# obd25k80.net
KiCad netlist of a schematic drawn in EAGLE
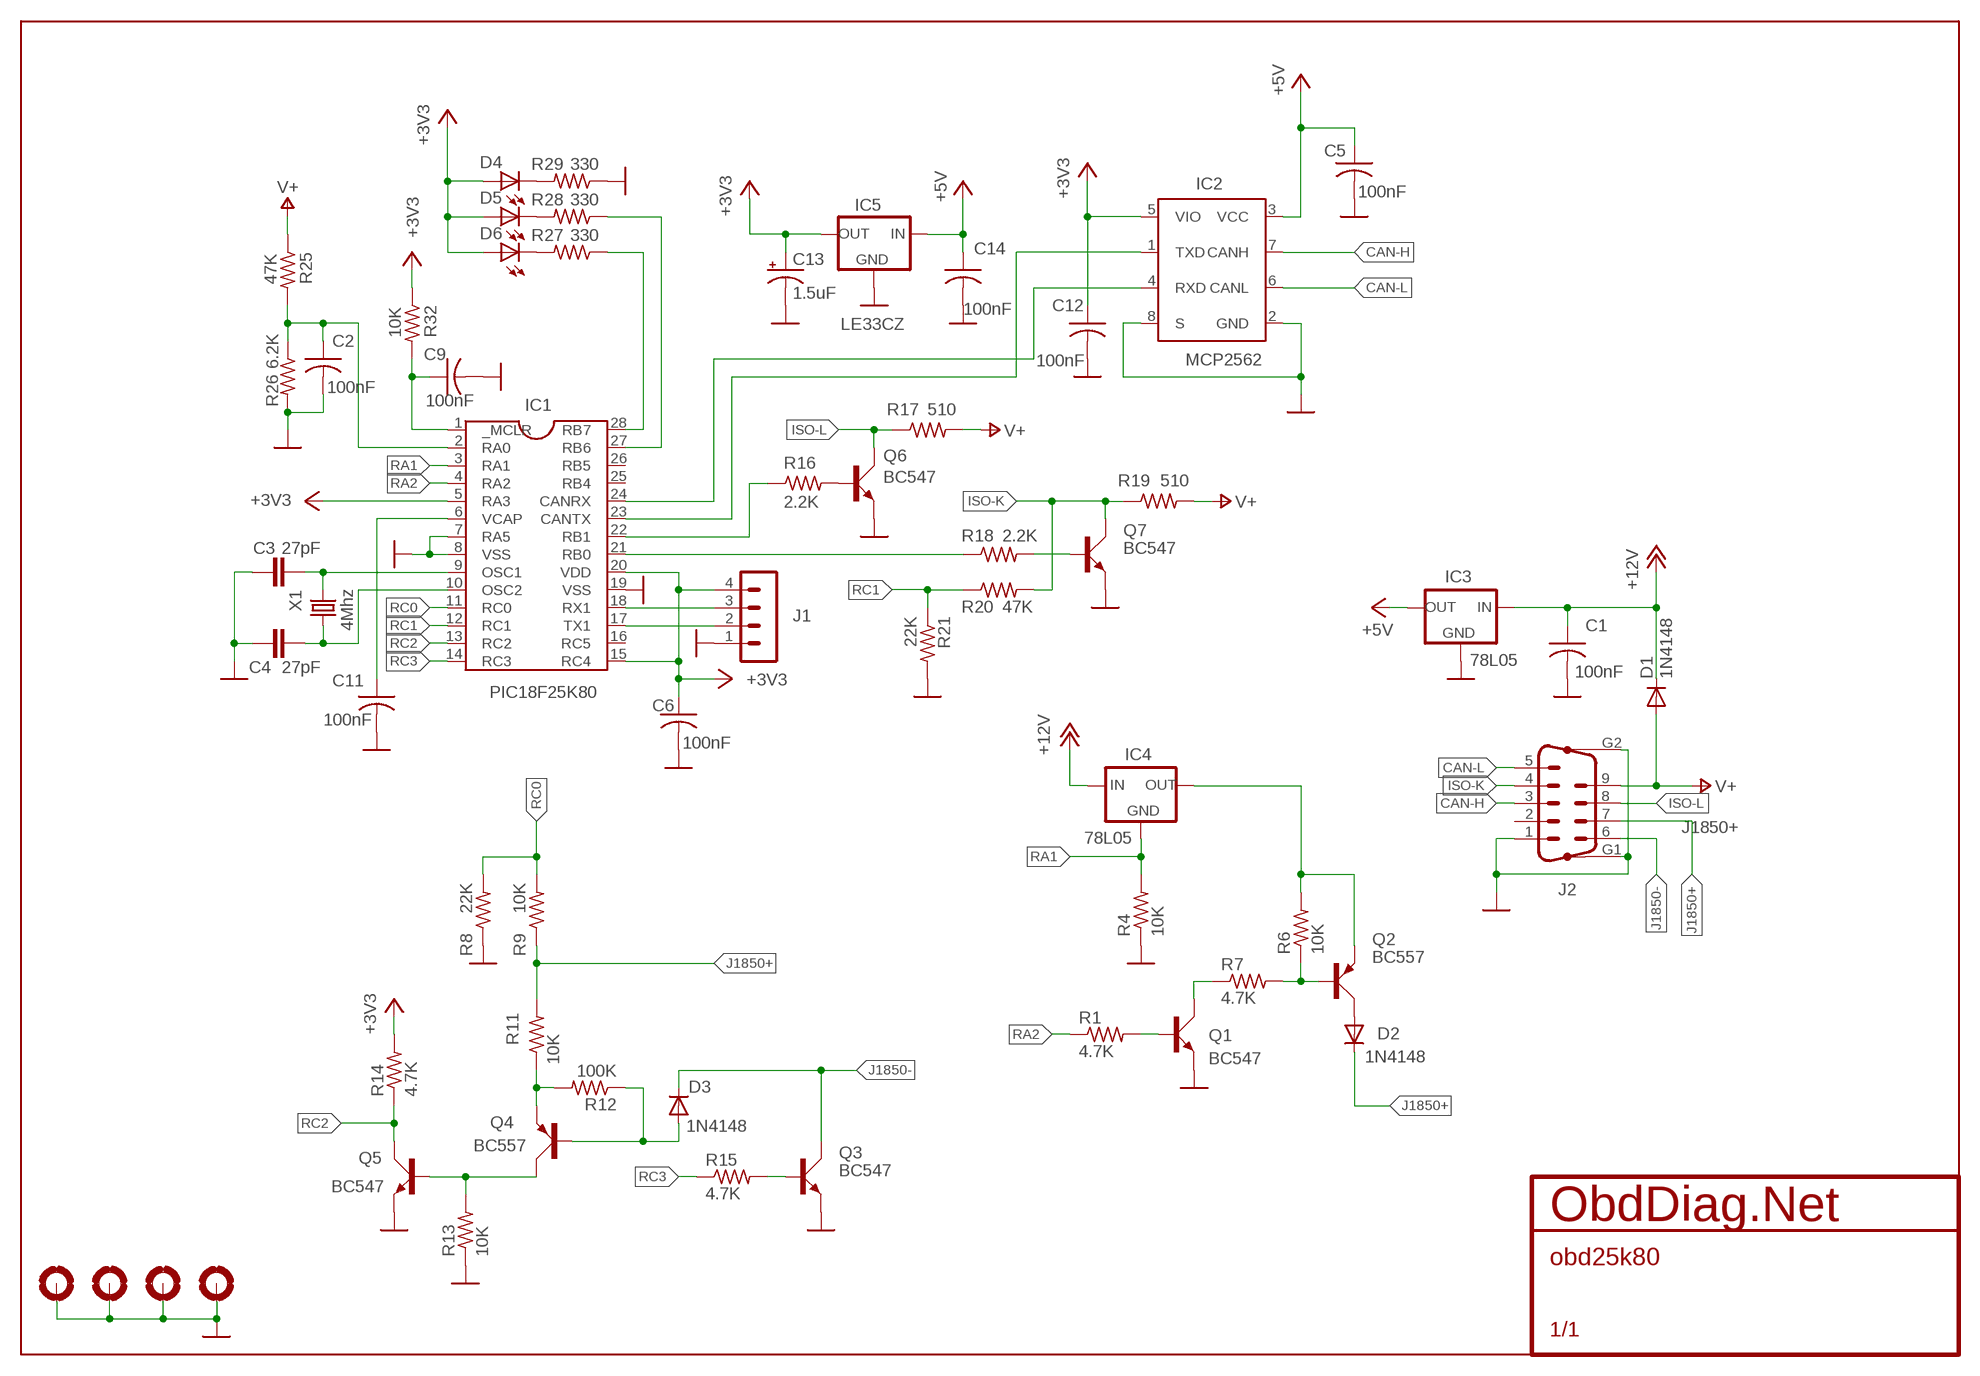
[diagram p0: schematic, sheet 1]

(export (version "E")
  (design (tool "Eeschema 10.0.6"))
  (components
    (comp (ref "C1")
      (value "100nF")
      (footprint "eagle-import:C050-025X075")
      (libsource (lib "eagle-import") (part "C-US050-025X075"))
    )
    (comp (ref "C2")
      (value "100nF")
      (footprint "eagle-import:C050-025X075")
      (libsource (lib "eagle-import") (part "C-US050-025X075"))
    )
    (comp (ref "C3")
      (value "27pF")
      (footprint "eagle-import:C2.5-2")
      (libsource (lib "eagle-import") (part "C2.5/2"))
    )
    (comp (ref "C4")
      (value "27pF")
      (footprint "eagle-import:C2.5-2")
      (libsource (lib "eagle-import") (part "C2.5/2"))
    )
    (comp (ref "C5")
      (value "100nF")
      (footprint "eagle-import:C050-025X075")
      (libsource (lib "eagle-import") (part "C-US050-025X075"))
    )
    (comp (ref "C6")
      (value "100nF")
      (footprint "eagle-import:C050-025X075")
      (libsource (lib "eagle-import") (part "C-US050-025X075"))
    )
    (comp (ref "C9")
      (value "100nF")
      (footprint "eagle-import:C050-025X075")
      (libsource (lib "eagle-import") (part "C-US050-025X075"))
    )
    (comp (ref "C11")
      (value "100nF")
      (footprint "eagle-import:C050-025X075")
      (libsource (lib "eagle-import") (part "C-US050-025X075"))
    )
    (comp (ref "C12")
      (value "100nF")
      (footprint "eagle-import:C050-025X075")
      (libsource (lib "eagle-import") (part "C-US050-025X075"))
    )
    (comp (ref "C13")
      (value "1.5uF")
      (footprint "eagle-import:E2,5-5")
      (libsource (lib "eagle-import") (part "CPOL-USE2.5-5"))
    )
    (comp (ref "C14")
      (value "100nF")
      (footprint "eagle-import:C050-025X075")
      (libsource (lib "eagle-import") (part "C-US050-025X075"))
    )
    (comp (ref "D1")
      (value "1N4148")
      (footprint "eagle-import:D035-10M")
      (libsource (lib "eagle-import") (part "1N4148M"))
    )
    (comp (ref "D2")
      (value "1N4148")
      (footprint "eagle-import:D035-10M")
      (libsource (lib "eagle-import") (part "1N4148M"))
    )
    (comp (ref "D3")
      (value "1N4148")
      (footprint "eagle-import:D035-10M")
      (libsource (lib "eagle-import") (part "1N4148M"))
    )
    (comp (ref "D4")
      (value "LED5MM")
      (footprint "eagle-import:LED5MM")
      (libsource (lib "eagle-import") (part "LED5MM"))
    )
    (comp (ref "D5")
      (value "LED5MM")
      (footprint "eagle-import:LED5MM")
      (libsource (lib "eagle-import") (part "LED5MM"))
    )
    (comp (ref "D6")
      (value "LED5MM")
      (footprint "eagle-import:LED5MM")
      (libsource (lib "eagle-import") (part "LED5MM"))
    )
    (comp (ref "H1")
      (value "MOUNT-PAD-ROUND2.8")
      (footprint "eagle-import:2,8-PAD")
      (libsource (lib "eagle-import") (part "MOUNT-PAD-ROUND2.8"))
    )
    (comp (ref "H2")
      (value "MOUNT-PAD-ROUND2.8")
      (footprint "eagle-import:2,8-PAD")
      (libsource (lib "eagle-import") (part "MOUNT-PAD-ROUND2.8"))
    )
    (comp (ref "H3")
      (value "MOUNT-PAD-ROUND2.8")
      (footprint "eagle-import:2,8-PAD")
      (libsource (lib "eagle-import") (part "MOUNT-PAD-ROUND2.8"))
    )
    (comp (ref "H4")
      (value "MOUNT-PAD-ROUND2.8")
      (footprint "eagle-import:2,8-PAD")
      (libsource (lib "eagle-import") (part "MOUNT-PAD-ROUND2.8"))
    )
    (comp (ref "IC1")
      (value "PIC18F25K80")
      (footprint "eagle-import:DIL28")
      (libsource (lib "eagle-import") (part "PIC18F25K80"))
    )
    (comp (ref "IC2")
      (value "MCP2562")
      (footprint "eagle-import:DIL8")
      (libsource (lib "eagle-import") (part "MCP2562"))
    )
    (comp (ref "IC3")
      (value "78L05")
      (footprint "eagle-import:78LXX")
      (libsource (lib "eagle-import") (part "78LXX"))
    )
    (comp (ref "IC4")
      (value "78L05")
      (footprint "eagle-import:78LXX")
      (libsource (lib "eagle-import") (part "78LXX"))
    )
    (comp (ref "IC5")
      (value "LE33CZ")
      (footprint "eagle-import:78LXX")
      (libsource (lib "eagle-import") (part "78LXX"))
    )
    (comp (ref "J1")
      (value "MA04-1")
      (footprint "eagle-import:MA04-1")
      (libsource (lib "eagle-import") (part "MA04-1"))
    )
    (comp (ref "J2")
      (value "DB9-M")
      (footprint "eagle-import:M09HP")
      (libsource (lib "eagle-import") (part "M09HP"))
    )
    (comp (ref "Q1")
      (value "BC547")
      (footprint "eagle-import:SOT54A")
      (libsource (lib "eagle-import") (part "BC547"))
    )
    (comp (ref "Q2")
      (value "BC557")
      (footprint "eagle-import:SOT54A")
      (libsource (lib "eagle-import") (part "BC557"))
    )
    (comp (ref "Q3")
      (value "BC547")
      (footprint "eagle-import:SOT54A")
      (libsource (lib "eagle-import") (part "BC547"))
    )
    (comp (ref "Q4")
      (value "BC557")
      (footprint "eagle-import:SOT54A")
      (libsource (lib "eagle-import") (part "BC557"))
    )
    (comp (ref "Q5")
      (value "BC547")
      (footprint "eagle-import:SOT54A")
      (libsource (lib "eagle-import") (part "BC547"))
    )
    (comp (ref "Q6")
      (value "BC547")
      (footprint "eagle-import:SOT54A")
      (libsource (lib "eagle-import") (part "BC547"))
    )
    (comp (ref "Q7")
      (value "BC547")
      (footprint "eagle-import:SOT54A")
      (libsource (lib "eagle-import") (part "BC547"))
    )
    (comp (ref "R1")
      (value "4.7K")
      (footprint "eagle-import:0207_10")
      (libsource (lib "eagle-import") (part "R-US_0207/10"))
    )
    (comp (ref "R4")
      (value "10K")
      (footprint "eagle-import:0207_10")
      (libsource (lib "eagle-import") (part "R-US_0207/10"))
    )
    (comp (ref "R6")
      (value "10K")
      (footprint "eagle-import:0207_10")
      (libsource (lib "eagle-import") (part "R-US_0207/10"))
    )
    (comp (ref "R7")
      (value "4.7K")
      (footprint "eagle-import:0207_10")
      (libsource (lib "eagle-import") (part "R-US_0207/10"))
    )
    (comp (ref "R8")
      (value "22K")
      (footprint "eagle-import:0207_10")
      (libsource (lib "eagle-import") (part "R-US_0207/10"))
    )
    (comp (ref "R9")
      (value "10K")
      (footprint "eagle-import:0207_10")
      (libsource (lib "eagle-import") (part "R-US_0207/10"))
    )
    (comp (ref "R11")
      (value "10K")
      (footprint "eagle-import:0207_10")
      (libsource (lib "eagle-import") (part "R-US_0207/10"))
    )
    (comp (ref "R12")
      (value "100K")
      (footprint "eagle-import:0207_10")
      (libsource (lib "eagle-import") (part "R-US_0207/10"))
    )
    (comp (ref "R13")
      (value "10K")
      (footprint "eagle-import:0207_10")
      (libsource (lib "eagle-import") (part "R-US_0207/10"))
    )
    (comp (ref "R14")
      (value "4.7K")
      (footprint "eagle-import:0207_10")
      (libsource (lib "eagle-import") (part "R-US_0207/10"))
    )
    (comp (ref "R15")
      (value "4.7K")
      (footprint "eagle-import:0207_10")
      (libsource (lib "eagle-import") (part "R-US_0207/10"))
    )
    (comp (ref "R16")
      (value "2.2K")
      (footprint "eagle-import:0207_10")
      (libsource (lib "eagle-import") (part "R-US_0207/10"))
    )
    (comp (ref "R17")
      (value "510")
      (footprint "eagle-import:0207_10")
      (libsource (lib "eagle-import") (part "R-US_0207/10"))
    )
    (comp (ref "R18")
      (value "2.2K")
      (footprint "eagle-import:0207_10")
      (libsource (lib "eagle-import") (part "R-US_0207/10"))
    )
    (comp (ref "R19")
      (value "510")
      (footprint "eagle-import:0207_10")
      (libsource (lib "eagle-import") (part "R-US_0207/10"))
    )
    (comp (ref "R20")
      (value "47K")
      (footprint "eagle-import:0207_10")
      (libsource (lib "eagle-import") (part "R-US_0207/10"))
    )
    (comp (ref "R21")
      (value "22K")
      (footprint "eagle-import:0207_10")
      (libsource (lib "eagle-import") (part "R-US_0207/10"))
    )
    (comp (ref "R25")
      (value "47K")
      (footprint "eagle-import:0207_10")
      (libsource (lib "eagle-import") (part "R-US_0207/10"))
    )
    (comp (ref "R26")
      (value "6.2K")
      (footprint "eagle-import:0207_10")
      (libsource (lib "eagle-import") (part "R-US_0207/10"))
    )
    (comp (ref "R27")
      (value "330")
      (footprint "eagle-import:0207_10")
      (libsource (lib "eagle-import") (part "R-US_0207/10"))
    )
    (comp (ref "R28")
      (value "330")
      (footprint "eagle-import:0207_10")
      (libsource (lib "eagle-import") (part "R-US_0207/10"))
    )
    (comp (ref "R29")
      (value "330")
      (footprint "eagle-import:0207_10")
      (libsource (lib "eagle-import") (part "R-US_0207/10"))
    )
    (comp (ref "R32")
      (value "10K")
      (footprint "eagle-import:0207_10")
      (libsource (lib "eagle-import") (part "R-US_0207/10"))
    )
    (comp (ref "X1")
      (value "4Mhz")
      (footprint "eagle-import:HC49_S")
      (libsource (lib "eagle-import") (part "CRYTALHC49S"))
    )
  )
  (nets
    (net (code "1") (name "+3V3") (class "Default")
      (node (ref "C12") (pin "1") (pinfunction "1_1") (pintype "passive"))
      (node (ref "C13") (pin "+") (pinfunction "+_+") (pintype "passive"))
      (node (ref "C6") (pin "1") (pinfunction "1_1") (pintype "passive"))
      (node (ref "D4") (pin "A") (pinfunction "A_A") (pintype "passive"))
      (node (ref "D5") (pin "A") (pinfunction "A_A") (pintype "passive"))
      (node (ref "D6") (pin "A") (pinfunction "A_A") (pintype "passive"))
      (node (ref "IC1") (pin "15") (pinfunction "RC4_15") (pintype "bidirectional"))
      (node (ref "IC1") (pin "20") (pinfunction "VDD_20") (pintype "power_in"))
      (node (ref "IC1") (pin "5") (pinfunction "RA3_5") (pintype "bidirectional"))
      (node (ref "IC2") (pin "5") (pinfunction "VIO_5") (pintype "power_in"))
      (node (ref "IC5") (pin "OUT") (pinfunction "OUT_OUT") (pintype "passive"))
      (node (ref "J1") (pin "4") (pinfunction "4_4") (pintype "passive"))
      (node (ref "R14") (pin "2") (pinfunction "2_2") (pintype "passive"))
      (node (ref "R32") (pin "1") (pinfunction "1_1") (pintype "passive"))
    )
    (net (code "2") (name "+5V") (class "Default")
      (node (ref "C14") (pin "1") (pinfunction "1_1") (pintype "passive"))
      (node (ref "C5") (pin "1") (pinfunction "1_1") (pintype "passive"))
      (node (ref "IC2") (pin "3") (pinfunction "VCC_3") (pintype "power_in"))
      (node (ref "IC3") (pin "OUT") (pinfunction "OUT_OUT") (pintype "passive"))
      (node (ref "IC5") (pin "IN") (pinfunction "IN_IN") (pintype "input"))
    )
    (net (code "3") (name "+12V") (class "Default")
      (node (ref "C1") (pin "1") (pinfunction "1_1") (pintype "passive"))
      (node (ref "D1") (pin "C") (pinfunction "C_C") (pintype "passive"))
      (node (ref "IC3") (pin "IN") (pinfunction "IN_IN") (pintype "input"))
      (node (ref "IC4") (pin "IN") (pinfunction "IN_IN") (pintype "input"))
    )
    (net (code "4") (name "CAN-H") (class "Default")
      (node (ref "IC2") (pin "7") (pinfunction "CANH_7") (pintype "bidirectional"))
      (node (ref "J2") (pin "3") (pinfunction "3_3") (pintype "passive"))
    )
    (net (code "5") (name "CAN-L") (class "Default")
      (node (ref "IC2") (pin "6") (pinfunction "CANL_6") (pintype "bidirectional"))
      (node (ref "J2") (pin "5") (pinfunction "5_5") (pintype "passive"))
    )
    (net (code "6") (name "GND") (class "Default")
      (node (ref "C1") (pin "2") (pinfunction "2_2") (pintype "passive"))
      (node (ref "C11") (pin "2") (pinfunction "2_2") (pintype "passive"))
      (node (ref "C12") (pin "2") (pinfunction "2_2") (pintype "passive"))
      (node (ref "C13") (pin "-") (pinfunction "-_-") (pintype "passive"))
      (node (ref "C14") (pin "2") (pinfunction "2_2") (pintype "passive"))
      (node (ref "C2") (pin "2") (pinfunction "2_2") (pintype "passive"))
      (node (ref "C3") (pin "1") (pinfunction "1_1") (pintype "passive"))
      (node (ref "C4") (pin "2") (pinfunction "2_2") (pintype "passive"))
      (node (ref "C5") (pin "2") (pinfunction "2_2") (pintype "passive"))
      (node (ref "C6") (pin "2") (pinfunction "2_2") (pintype "passive"))
      (node (ref "C9") (pin "2") (pinfunction "2_2") (pintype "passive"))
      (node (ref "H1") (pin "B2,8") (pinfunction "MOUNT_B2,8") (pintype "passive"))
      (node (ref "H2") (pin "B2,8") (pinfunction "MOUNT_B2,8") (pintype "passive"))
      (node (ref "H3") (pin "B2,8") (pinfunction "MOUNT_B2,8") (pintype "passive"))
      (node (ref "H4") (pin "B2,8") (pinfunction "MOUNT_B2,8") (pintype "passive"))
      (node (ref "IC1") (pin "19") (pinfunction "VSS_19") (pintype "power_in"))
      (node (ref "IC1") (pin "7") (pinfunction "RA5_7") (pintype "bidirectional"))
      (node (ref "IC1") (pin "8") (pinfunction "VSS_8") (pintype "power_in"))
      (node (ref "IC2") (pin "2") (pinfunction "GND_2") (pintype "power_in"))
      (node (ref "IC2") (pin "8") (pinfunction "S_8") (pintype "input"))
      (node (ref "IC3") (pin "GND") (pinfunction "GND_GND") (pintype "input"))
      (node (ref "IC5") (pin "GND") (pinfunction "GND_GND") (pintype "input"))
      (node (ref "J1") (pin "1") (pinfunction "1_1") (pintype "passive"))
      (node (ref "J2") (pin "1") (pinfunction "1_1") (pintype "passive"))
      (node (ref "J2") (pin "G1") (pinfunction "G1_G1") (pintype "passive"))
      (node (ref "J2") (pin "G2") (pinfunction "G2_G2") (pintype "passive"))
      (node (ref "Q1") (pin "E") (pinfunction "E_E") (pintype "passive"))
      (node (ref "Q3") (pin "E") (pinfunction "E_E") (pintype "passive"))
      (node (ref "Q5") (pin "E") (pinfunction "E_E") (pintype "passive"))
      (node (ref "Q6") (pin "E") (pinfunction "E_E") (pintype "passive"))
      (node (ref "Q7") (pin "E") (pinfunction "E_E") (pintype "passive"))
      (node (ref "R13") (pin "1") (pinfunction "1_1") (pintype "passive"))
      (node (ref "R21") (pin "2") (pinfunction "2_2") (pintype "passive"))
      (node (ref "R26") (pin "2") (pinfunction "2_2") (pintype "passive"))
      (node (ref "R29") (pin "1") (pinfunction "1_1") (pintype "passive"))
      (node (ref "R4") (pin "1") (pinfunction "1_1") (pintype "passive"))
      (node (ref "R8") (pin "1") (pinfunction "1_1") (pintype "passive"))
    )
    (net (code "7") (name "ISO-K") (class "Default")
      (node (ref "J2") (pin "4") (pinfunction "4_4") (pintype "passive"))
      (node (ref "Q7") (pin "C") (pinfunction "C_C") (pintype "passive"))
      (node (ref "R19") (pin "1") (pinfunction "1_1") (pintype "passive"))
      (node (ref "R20") (pin "2") (pinfunction "2_2") (pintype "passive"))
    )
    (net (code "8") (name "ISO-L") (class "Default")
      (node (ref "J2") (pin "8") (pinfunction "8_8") (pintype "passive"))
      (node (ref "Q6") (pin "C") (pinfunction "C_C") (pintype "passive"))
      (node (ref "R17") (pin "1") (pinfunction "1_1") (pintype "passive"))
    )
    (net (code "9") (name "J1850+") (class "Default")
      (node (ref "D2") (pin "C") (pinfunction "C_C") (pintype "passive"))
      (node (ref "J2") (pin "7") (pinfunction "7_7") (pintype "passive"))
      (node (ref "R11") (pin "2") (pinfunction "2_2") (pintype "passive"))
      (node (ref "R9") (pin "1") (pinfunction "1_1") (pintype "passive"))
    )
    (net (code "10") (name "J1850-") (class "Default")
      (node (ref "D3") (pin "C") (pinfunction "C_C") (pintype "passive"))
      (node (ref "J2") (pin "6") (pinfunction "6_6") (pintype "passive"))
      (node (ref "Q3") (pin "C") (pinfunction "C_C") (pintype "passive"))
    )
    (net (code "11") (name "Net-(D2-PadA)") (class "Default")
      (node (ref "D2") (pin "A") (pinfunction "A_A") (pintype "passive"))
      (node (ref "Q2") (pin "C") (pinfunction "C_C") (pintype "passive"))
    )
    (net (code "12") (name "Net-(D3-PadA)") (class "Default")
      (node (ref "D3") (pin "A") (pinfunction "A_A") (pintype "passive"))
      (node (ref "Q4") (pin "B") (pinfunction "B_B") (pintype "passive"))
      (node (ref "R12") (pin "1") (pinfunction "1_1") (pintype "passive"))
    )
    (net (code "13") (name "Net-(D4-C)") (class "Default")
      (node (ref "D4") (pin "K") (pinfunction "C_K") (pintype "passive"))
      (node (ref "R29") (pin "2") (pinfunction "2_2") (pintype "passive"))
    )
    (net (code "14") (name "Net-(D5-C)") (class "Default")
      (node (ref "D5") (pin "K") (pinfunction "C_K") (pintype "passive"))
      (node (ref "R28") (pin "2") (pinfunction "2_2") (pintype "passive"))
    )
    (net (code "15") (name "Net-(D6-C)") (class "Default")
      (node (ref "D6") (pin "K") (pinfunction "C_K") (pintype "passive"))
      (node (ref "R27") (pin "2") (pinfunction "2_2") (pintype "passive"))
    )
    (net (code "16") (name "Net-(IC1-CANRX)") (class "Default")
      (node (ref "IC1") (pin "24") (pinfunction "CANRX_24") (pintype "bidirectional"))
      (node (ref "IC2") (pin "4") (pinfunction "RXD_4") (pintype "output"))
    )
    (net (code "17") (name "Net-(IC1-CANTX)") (class "Default")
      (node (ref "IC1") (pin "23") (pinfunction "CANTX_23") (pintype "bidirectional"))
      (node (ref "IC2") (pin "1") (pinfunction "TXD_1") (pintype "input"))
    )
    (net (code "18") (name "Net-(IC1-OSC1)") (class "Default")
      (node (ref "C3") (pin "2") (pinfunction "2_2") (pintype "passive"))
      (node (ref "IC1") (pin "9") (pinfunction "OSC1_9") (pintype "bidirectional"))
      (node (ref "X1") (pin "2") (pinfunction "2_2") (pintype "passive"))
    )
    (net (code "19") (name "Net-(IC1-OSC2)") (class "Default")
      (node (ref "C4") (pin "1") (pinfunction "1_1") (pintype "passive"))
      (node (ref "IC1") (pin "10") (pinfunction "OSC2_10") (pintype "bidirectional"))
      (node (ref "X1") (pin "1") (pinfunction "1_1") (pintype "passive"))
    )
    (net (code "20") (name "Net-(IC1-RA0)") (class "Default")
      (node (ref "C2") (pin "1") (pinfunction "1_1") (pintype "passive"))
      (node (ref "IC1") (pin "2") (pinfunction "RA0_2") (pintype "bidirectional"))
      (node (ref "R25") (pin "2") (pinfunction "2_2") (pintype "passive"))
      (node (ref "R26") (pin "1") (pinfunction "1_1") (pintype "passive"))
    )
    (net (code "21") (name "Net-(IC1-RB0)") (class "Default")
      (node (ref "IC1") (pin "21") (pinfunction "RB0_21") (pintype "bidirectional"))
      (node (ref "R18") (pin "1") (pinfunction "1_1") (pintype "passive"))
    )
    (net (code "22") (name "Net-(IC1-RB1)") (class "Default")
      (node (ref "IC1") (pin "22") (pinfunction "RB1_22") (pintype "bidirectional"))
      (node (ref "R16") (pin "1") (pinfunction "1_1") (pintype "passive"))
    )
    (net (code "23") (name "Net-(IC1-RB6)") (class "Default")
      (node (ref "IC1") (pin "27") (pinfunction "RB6_27") (pintype "bidirectional"))
      (node (ref "R28") (pin "1") (pinfunction "1_1") (pintype "passive"))
    )
    (net (code "24") (name "Net-(IC1-RB7)") (class "Default")
      (node (ref "IC1") (pin "28") (pinfunction "RB7_28") (pintype "bidirectional"))
      (node (ref "R27") (pin "1") (pinfunction "1_1") (pintype "passive"))
    )
    (net (code "25") (name "Net-(IC1-RX1)") (class "Default")
      (node (ref "IC1") (pin "18") (pinfunction "RX1_18") (pintype "bidirectional"))
      (node (ref "J1") (pin "3") (pinfunction "3_3") (pintype "passive"))
    )
    (net (code "26") (name "Net-(IC1-TX1)") (class "Default")
      (node (ref "IC1") (pin "17") (pinfunction "TX1_17") (pintype "bidirectional"))
      (node (ref "J1") (pin "2") (pinfunction "2_2") (pintype "passive"))
    )
    (net (code "27") (name "Net-(IC1-VCAP)") (class "Default")
      (node (ref "C11") (pin "1") (pinfunction "1_1") (pintype "passive"))
      (node (ref "IC1") (pin "6") (pinfunction "VCAP_6") (pintype "passive"))
    )
    (net (code "28") (name "Net-(IC1-_MCLR)") (class "Default")
      (node (ref "C9") (pin "1") (pinfunction "1_1") (pintype "passive"))
      (node (ref "IC1") (pin "1") (pinfunction "_MCLR_1") (pintype "bidirectional"))
      (node (ref "R32") (pin "2") (pinfunction "2_2") (pintype "passive"))
    )
    (net (code "29") (name "Net-(IC4-PadOUT)") (class "Default")
      (node (ref "IC4") (pin "OUT") (pinfunction "OUT_OUT") (pintype "passive"))
      (node (ref "Q2") (pin "E") (pinfunction "E_E") (pintype "passive"))
      (node (ref "R6") (pin "2") (pinfunction "2_2") (pintype "passive"))
    )
    (net (code "30") (name "Net-(Q1-PadB)") (class "Default")
      (node (ref "Q1") (pin "B") (pinfunction "B_B") (pintype "passive"))
      (node (ref "R1") (pin "2") (pinfunction "2_2") (pintype "passive"))
    )
    (net (code "31") (name "Net-(Q1-PadC)") (class "Default")
      (node (ref "Q1") (pin "C") (pinfunction "C_C") (pintype "passive"))
      (node (ref "R7") (pin "1") (pinfunction "1_1") (pintype "passive"))
    )
    (net (code "32") (name "Net-(Q2-PadB)") (class "Default")
      (node (ref "Q2") (pin "B") (pinfunction "B_B") (pintype "passive"))
      (node (ref "R6") (pin "1") (pinfunction "1_1") (pintype "passive"))
      (node (ref "R7") (pin "2") (pinfunction "2_2") (pintype "passive"))
    )
    (net (code "33") (name "Net-(Q3-PadB)") (class "Default")
      (node (ref "Q3") (pin "B") (pinfunction "B_B") (pintype "passive"))
      (node (ref "R15") (pin "2") (pinfunction "2_2") (pintype "passive"))
    )
    (net (code "34") (name "Net-(Q4-PadC)") (class "Default")
      (node (ref "Q4") (pin "C") (pinfunction "C_C") (pintype "passive"))
      (node (ref "Q5") (pin "B") (pinfunction "B_B") (pintype "passive"))
      (node (ref "R13") (pin "2") (pinfunction "2_2") (pintype "passive"))
    )
    (net (code "35") (name "Net-(Q4-PadE)") (class "Default")
      (node (ref "Q4") (pin "E") (pinfunction "E_E") (pintype "passive"))
      (node (ref "R11") (pin "1") (pinfunction "1_1") (pintype "passive"))
      (node (ref "R12") (pin "2") (pinfunction "2_2") (pintype "passive"))
    )
    (net (code "36") (name "Net-(Q6-PadB)") (class "Default")
      (node (ref "Q6") (pin "B") (pinfunction "B_B") (pintype "passive"))
      (node (ref "R16") (pin "2") (pinfunction "2_2") (pintype "passive"))
    )
    (net (code "37") (name "Net-(Q7-PadB)") (class "Default")
      (node (ref "Q7") (pin "B") (pinfunction "B_B") (pintype "passive"))
      (node (ref "R18") (pin "2") (pinfunction "2_2") (pintype "passive"))
    )
    (net (code "38") (name "RA1") (class "Default")
      (node (ref "IC1") (pin "3") (pinfunction "RA1_3") (pintype "bidirectional"))
      (node (ref "IC4") (pin "GND") (pinfunction "GND_GND") (pintype "input"))
      (node (ref "R4") (pin "2") (pinfunction "2_2") (pintype "passive"))
    )
    (net (code "39") (name "RA2") (class "Default")
      (node (ref "IC1") (pin "4") (pinfunction "RA2_4") (pintype "bidirectional"))
      (node (ref "R1") (pin "1") (pinfunction "1_1") (pintype "passive"))
    )
    (net (code "40") (name "RC0") (class "Default")
      (node (ref "IC1") (pin "11") (pinfunction "RC0_11") (pintype "bidirectional"))
      (node (ref "R8") (pin "2") (pinfunction "2_2") (pintype "passive"))
      (node (ref "R9") (pin "2") (pinfunction "2_2") (pintype "passive"))
    )
    (net (code "41") (name "RC1") (class "Default")
      (node (ref "IC1") (pin "12") (pinfunction "RC1_12") (pintype "bidirectional"))
      (node (ref "R20") (pin "1") (pinfunction "1_1") (pintype "passive"))
      (node (ref "R21") (pin "1") (pinfunction "1_1") (pintype "passive"))
    )
    (net (code "42") (name "RC2") (class "Default")
      (node (ref "IC1") (pin "13") (pinfunction "RC2_13") (pintype "bidirectional"))
      (node (ref "Q5") (pin "C") (pinfunction "C_C") (pintype "passive"))
      (node (ref "R14") (pin "1") (pinfunction "1_1") (pintype "passive"))
    )
    (net (code "43") (name "RC3") (class "Default")
      (node (ref "IC1") (pin "14") (pinfunction "RC3_14") (pintype "bidirectional"))
      (node (ref "R15") (pin "1") (pinfunction "1_1") (pintype "passive"))
    )
    (net (code "44") (name "V+") (class "Default")
      (node (ref "D1") (pin "A") (pinfunction "A_A") (pintype "passive"))
      (node (ref "J2") (pin "9") (pinfunction "9_9") (pintype "passive"))
      (node (ref "R17") (pin "2") (pinfunction "2_2") (pintype "passive"))
      (node (ref "R19") (pin "2") (pinfunction "2_2") (pintype "passive"))
      (node (ref "R25") (pin "1") (pinfunction "1_1") (pintype "passive"))
    )
    (net (code "45") (name "unconnected-(IC1-RB4-Pad25)") (class "Default")
      (node (ref "IC1") (pin "25") (pinfunction "RB4_25") (pintype "bidirectional"))
    )
    (net (code "46") (name "unconnected-(IC1-RB5-Pad26)") (class "Default")
      (node (ref "IC1") (pin "26") (pinfunction "RB5_26") (pintype "bidirectional"))
    )
    (net (code "47") (name "unconnected-(IC1-RC5-Pad16)") (class "Default")
      (node (ref "IC1") (pin "16") (pinfunction "RC5_16") (pintype "bidirectional"))
    )
    (net (code "48") (name "unconnected-(J2-Pad2)") (class "Default")
      (node (ref "J2") (pin "2") (pinfunction "2_2") (pintype "passive"))
    )
  )
)
